# display.net
KiCad netlist of a schematic drawn in Altium Designer
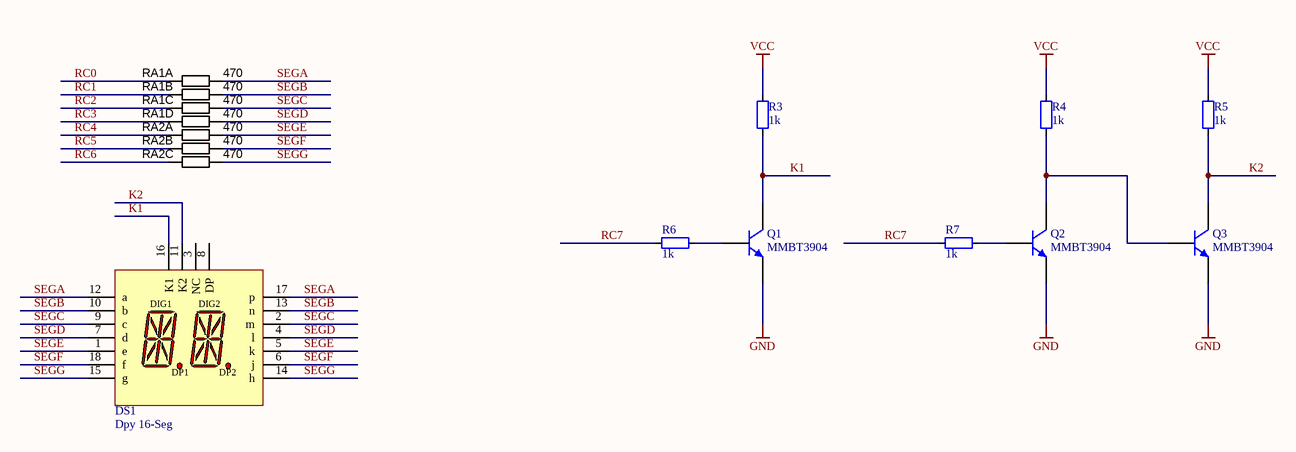
[diagram p0: display.SchDoc]

(export (version "E")
  (design (tool "Eeschema 10.0.6"))
  (components
    (comp (ref "DS1")
      (value "Dpy 16-Seg")
      (footprint "HDSP-A2")
      (description "13.7 mm Gray Surface As AlInGaP Red Alphanumeric Display: 2-Character, CC")
      (fields (field (name "PUBLISHER") "Altium Limited"))
      (libsource (lib "Miscellaneous Devices") (part "Dpy 16-Seg"))
    )
    (comp (ref "Q1")
      (value "MMBT3904")
      (footprint "SOT23_N")
      (description "NPN Switching Transistor")
      (fields (field (name "PUBLISHER") "Altium Limited"))
      (libsource (lib "Philips Discrete BJT - Low Power") (part "MMBT3904"))
    )
    (comp (ref "Q2")
      (value "MMBT3904")
      (footprint "SOT23_N")
      (description "NPN Switching Transistor")
      (fields (field (name "PUBLISHER") "Altium Limited"))
      (libsource (lib "Philips Discrete BJT - Low Power") (part "MMBT3904"))
    )
    (comp (ref "Q3")
      (value "MMBT3904")
      (footprint "SOT23_N")
      (description "NPN Switching Transistor")
      (fields (field (name "PUBLISHER") "Altium Limited"))
      (libsource (lib "Philips Discrete BJT - Low Power") (part "MMBT3904"))
    )
    (comp (ref "R3")
      (value "1k")
      (footprint "PCB_PassiveRes:RES_0603")
      (description "Resistor")
      (fields (field (name "Comment") "Res_0603"))
      (libsource (lib "SCH_Passive") (part "Res_0603"))
    )
    (comp (ref "R4")
      (value "1k")
      (footprint "PCB_PassiveRes:RES_0603")
      (description "Resistor")
      (fields (field (name "Comment") "Res_0603"))
      (libsource (lib "SCH_Passive") (part "Res_0603"))
    )
    (comp (ref "R5")
      (value "1k")
      (footprint "PCB_PassiveRes:RES_0603")
      (description "Resistor")
      (fields (field (name "Comment") "Res_0603"))
      (libsource (lib "SCH_Passive") (part "Res_0603"))
    )
    (comp (ref "R6")
      (value "1k")
      (footprint "PCB_PassiveRes:RES_0603")
      (description "Resistor")
      (fields (field (name "Comment") "Res_0603"))
      (libsource (lib "") (part "Res_0603_1"))
    )
    (comp (ref "R7")
      (value "1k")
      (footprint "PCB_PassiveRes:RES_0603")
      (description "Resistor")
      (fields (field (name "Comment") "Res_0603"))
      (libsource (lib "") (part "Res_0603_1"))
    )
    (comp (ref "RA1")
      (value "470")
      (footprint "RESCAXS50P160X320X70-8N")
      (description "Resistor array 1K Ohm 4-pack 62.5mW 5% 4x1608 SMD")
      (fields (field (name "TOLERANCE") "±5%") (field (name "Comment") "Film Res Pack"))
      (libsource (lib "PBL - Resistors") (part "RESPACK_1K_5%_4X"))
    )
    (comp (ref "RA2")
      (value "470")
      (footprint "RESCAXS50P160X320X70-8N")
      (description "Resistor array 1K Ohm 4-pack 62.5mW 5% 4x1608 SMD")
      (fields (field (name "TOLERANCE") "±5%") (field (name "Comment") "Film Res Pack"))
      (libsource (lib "PBL - Resistors") (part "RESPACK_1K_5%_4X"))
    )
  )
  (nets
    (net (code "1") (name "/K1") (class "Default")
      (node (ref "DS1") (pin "16") (pinfunction "K1_16") (pintype "passive"))
      (node (ref "Q1") (pin "3") (pinfunction "C_3") (pintype "passive"))
      (node (ref "R3") (pin "1") (pinfunction "1_1") (pintype "passive"))
    )
    (net (code "2") (name "/K2") (class "Default")
      (node (ref "DS1") (pin "11") (pinfunction "K2_11") (pintype "passive"))
      (node (ref "Q3") (pin "3") (pinfunction "C_3") (pintype "passive"))
      (node (ref "R5") (pin "1") (pinfunction "1_1") (pintype "passive"))
    )
    (net (code "3") (name "/RC0") (class "Default")
      (node (ref "RA1") (pin "1") (pinfunction "1_1") (pintype "passive"))
    )
    (net (code "4") (name "/RC1") (class "Default")
      (node (ref "RA1") (pin "2") (pinfunction "2_2") (pintype "passive"))
    )
    (net (code "5") (name "/RC2") (class "Default")
      (node (ref "RA1") (pin "3") (pinfunction "3_3") (pintype "passive"))
    )
    (net (code "6") (name "/RC3") (class "Default")
      (node (ref "RA1") (pin "4") (pinfunction "4_4") (pintype "passive"))
    )
    (net (code "7") (name "/RC4") (class "Default")
      (node (ref "RA2") (pin "1") (pinfunction "1_1") (pintype "passive"))
    )
    (net (code "8") (name "/RC5") (class "Default")
      (node (ref "RA2") (pin "2") (pinfunction "2_2") (pintype "passive"))
    )
    (net (code "9") (name "/RC6") (class "Default")
      (node (ref "RA2") (pin "3") (pinfunction "3_3") (pintype "passive"))
    )
    (net (code "10") (name "/RC7") (class "Default")
      (node (ref "R6") (pin "2") (pinfunction "2_2") (pintype "passive"))
      (node (ref "R7") (pin "2") (pinfunction "2_2") (pintype "passive"))
    )
    (net (code "11") (name "/SEGA") (class "Default")
      (node (ref "DS1") (pin "12") (pinfunction "a_12") (pintype "passive"))
      (node (ref "DS1") (pin "17") (pinfunction "p_17") (pintype "passive"))
      (node (ref "RA1") (pin "8") (pinfunction "8_8") (pintype "passive"))
    )
    (net (code "12") (name "/SEGB") (class "Default")
      (node (ref "DS1") (pin "10") (pinfunction "b_10") (pintype "passive"))
      (node (ref "DS1") (pin "13") (pinfunction "n_13") (pintype "passive"))
      (node (ref "RA1") (pin "7") (pinfunction "7_7") (pintype "passive"))
    )
    (net (code "13") (name "/SEGC") (class "Default")
      (node (ref "DS1") (pin "2") (pinfunction "m_2") (pintype "passive"))
      (node (ref "DS1") (pin "9") (pinfunction "c_9") (pintype "passive"))
      (node (ref "RA1") (pin "6") (pinfunction "6_6") (pintype "passive"))
    )
    (net (code "14") (name "/SEGD") (class "Default")
      (node (ref "DS1") (pin "4") (pinfunction "l_4") (pintype "passive"))
      (node (ref "DS1") (pin "7") (pinfunction "d_7") (pintype "passive"))
      (node (ref "RA1") (pin "5") (pinfunction "5_5") (pintype "passive"))
    )
    (net (code "15") (name "/SEGE") (class "Default")
      (node (ref "DS1") (pin "1") (pinfunction "e_1") (pintype "passive"))
      (node (ref "DS1") (pin "5") (pinfunction "k_5") (pintype "passive"))
      (node (ref "RA2") (pin "8") (pinfunction "8_8") (pintype "passive"))
    )
    (net (code "16") (name "/SEGF") (class "Default")
      (node (ref "DS1") (pin "18") (pinfunction "f_18") (pintype "passive"))
      (node (ref "DS1") (pin "6") (pinfunction "j_6") (pintype "passive"))
      (node (ref "RA2") (pin "7") (pinfunction "7_7") (pintype "passive"))
    )
    (net (code "17") (name "/SEGG") (class "Default")
      (node (ref "DS1") (pin "14") (pinfunction "h_14") (pintype "passive"))
      (node (ref "DS1") (pin "15") (pinfunction "g_15") (pintype "passive"))
      (node (ref "RA2") (pin "6") (pinfunction "6_6") (pintype "passive"))
    )
    (net (code "18") (name "GND") (class "Default")
      (node (ref "Q1") (pin "2") (pinfunction "E_2") (pintype "passive"))
      (node (ref "Q2") (pin "2") (pinfunction "E_2") (pintype "passive"))
      (node (ref "Q3") (pin "2") (pinfunction "E_2") (pintype "passive"))
    )
    (net (code "19") (name "Net-(Q1-B)") (class "Default")
      (node (ref "Q1") (pin "1") (pinfunction "B_1") (pintype "passive"))
      (node (ref "R6") (pin "1") (pinfunction "1_1") (pintype "passive"))
    )
    (net (code "20") (name "Net-(Q2-B)") (class "Default")
      (node (ref "Q2") (pin "1") (pinfunction "B_1") (pintype "passive"))
      (node (ref "R7") (pin "1") (pinfunction "1_1") (pintype "passive"))
    )
    (net (code "21") (name "Net-(Q2-C)") (class "Default")
      (node (ref "Q2") (pin "3") (pinfunction "C_3") (pintype "passive"))
      (node (ref "Q3") (pin "1") (pinfunction "B_1") (pintype "passive"))
      (node (ref "R4") (pin "1") (pinfunction "1_1") (pintype "passive"))
    )
    (net (code "22") (name "VCC") (class "Default")
      (node (ref "R3") (pin "2") (pinfunction "2_2") (pintype "passive"))
      (node (ref "R4") (pin "2") (pinfunction "2_2") (pintype "passive"))
      (node (ref "R5") (pin "2") (pinfunction "2_2") (pintype "passive"))
    )
    (net (code "23") (name "unconnected-(DS1-DP-Pad8)") (class "Default")
      (node (ref "DS1") (pin "8") (pinfunction "DP_8") (pintype "passive"))
    )
    (net (code "24") (name "unconnected-(DS1-NC-Pad3)") (class "Default")
      (node (ref "DS1") (pin "3") (pinfunction "NC_3") (pintype "passive"))
    )
  )
)
